# POWER_NODE.net
KiCad netlist of a schematic drawn in Altium Designer
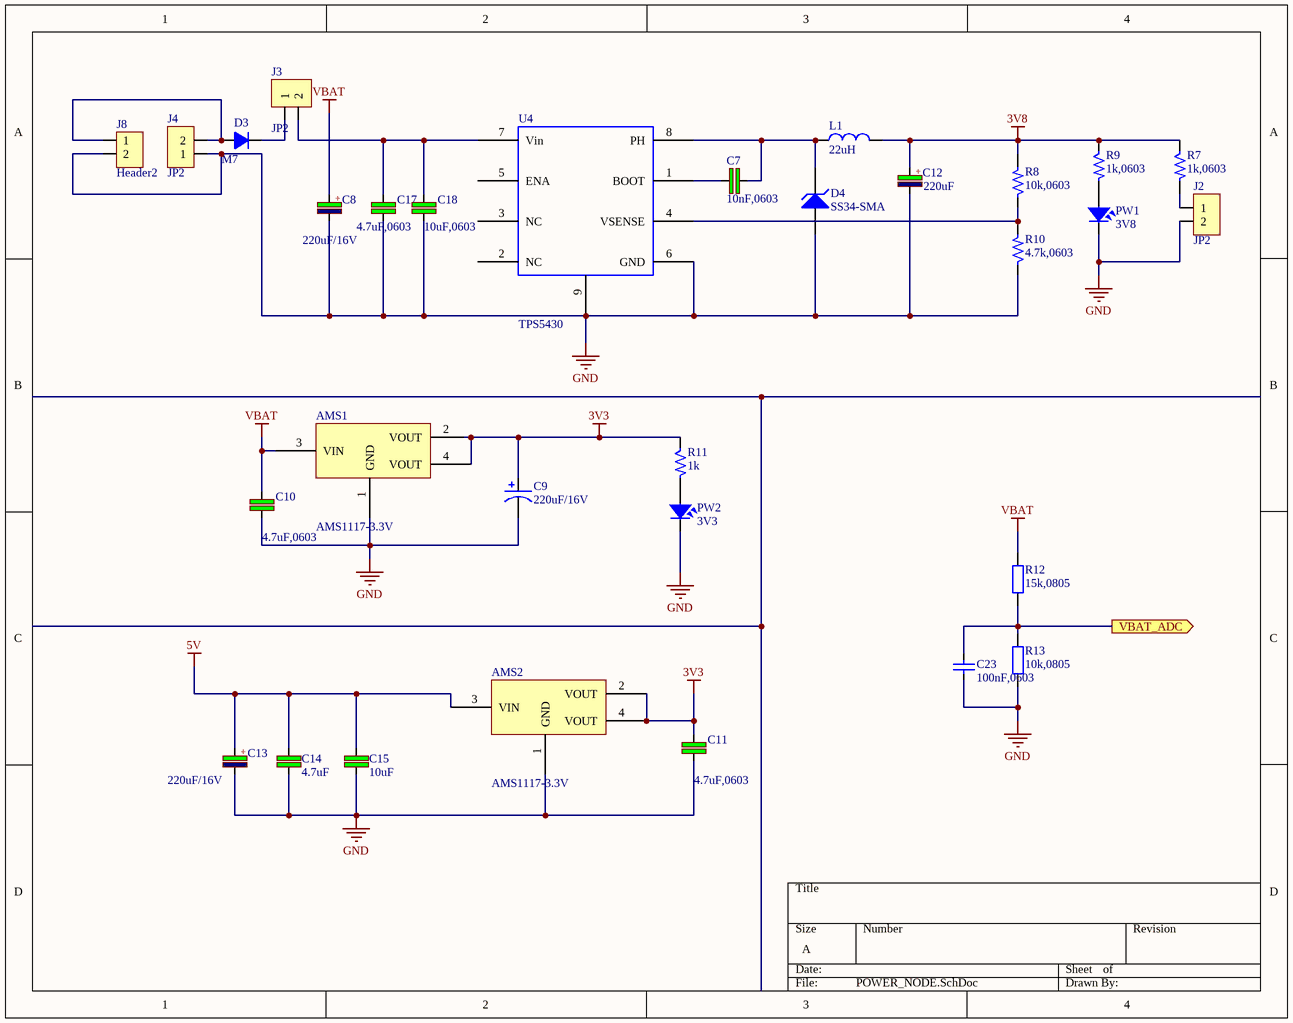
[diagram p0: POWER_NODE.SchDoc]

(export (version "E")
  (design (tool "Eeschema 10.0.6"))
  (components
    (comp (ref "AMS1")
      (value "AMS1117-3.3V")
      (footprint "SOT223")
      (description "Dán")
      (libsource (lib "IC") (part "AMS1117 SMD"))
    )
    (comp (ref "AMS2")
      (value "AMS1117-3.3V")
      (footprint "SOT223")
      (description "Dán")
      (libsource (lib "IC") (part "AMS1117 SMD"))
    )
    (comp (ref "C7")
      (value "10nF,0603")
      (footprint "CAP_0603")
      (description "4.7µF ±10% 35V Ceramic Capacitor X5R 0805 (2012 Metric)")
      (fields
        (field (name "MANUFACTURER") "Samsung Electro-Mechanics")
        (field (name "PART NUMBER") "CL21A475KLCLQNC")
      )
      (libsource (lib "Anh_Trung") (part "C"))
    )
    (comp (ref "C8")
      (value "220uF/16V")
      (footprint "C8mm")
      (description "Cap 470uF/63V")
      (libsource (lib "Main") (part "CP3"))
    )
    (comp (ref "C9")
      (value "220uF/16V")
      (footprint "C5mm")
      (description "Polarized Capacitor (Axial)")
      (fields (field (name "PUBLISHER") "Altium Limited"))
      (libsource (lib "My Library") (part "Cap Pol"))
    )
    (comp (ref "C10")
      (value "4.7uF,0603")
      (footprint "CAP_0603")
      (description "4.7µF ±10% 35V Ceramic Capacitor X5R 0805 (2012 Metric)")
      (fields
        (field (name "MANUFACTURER") "Samsung Electro-Mechanics")
        (field (name "PART NUMBER") "CL21A475KLCLQNC")
      )
      (libsource (lib "") (part "C_1"))
    )
    (comp (ref "C11")
      (value "4.7uF,0603")
      (footprint "CAP_0603")
      (description "4.7µF ±10% 35V Ceramic Capacitor X5R 0805 (2012 Metric)")
      (fields
        (field (name "MANUFACTURER") "Samsung Electro-Mechanics")
        (field (name "PART NUMBER") "CL21A475KLCLQNC")
      )
      (libsource (lib "") (part "C_1"))
    )
    (comp (ref "C12")
      (value "220uF")
      (footprint "C5mm")
      (description "220µF Molded Tantalum Polymer Capacitor 16V 2917 (7343 Metric) 40mOhm @ 100kHz")
      (fields
        (field (name "MANUFACTURER") "AVX Corporation")
        (field (name "PART NUMBER") "TCME227M016R0040E")
      )
      (libsource (lib "Anh_Trung") (part "CP5"))
    )
    (comp (ref "C13")
      (value "220uF/16V")
      (footprint "C8mm")
      (description "Cap 470uF/63V")
      (libsource (lib "Main") (part "CP3"))
    )
    (comp (ref "C14")
      (value "4.7uF")
      (footprint "CAP_0603")
      (description "Cap SMD")
      (fields
        (field (name "MANUFACTURER") "Samsung Electro-Mechanics")
        (field (name "PART NUMBER") "CL21A106KPFNNNG")
      )
      (libsource (lib "Anh_Trung") (part "C"))
    )
    (comp (ref "C15")
      (value "10uF")
      (footprint "CAP_0603")
      (description "Cap SMD")
      (fields
        (field (name "MANUFACTURER") "Samsung Electro-Mechanics")
        (field (name "PART NUMBER") "CL21A106KPFNNNG")
      )
      (libsource (lib "Anh_Trung") (part "C"))
    )
    (comp (ref "C17")
      (value "4.7uF,0603")
      (footprint "CAP_0603")
      (description "4.7µF ±10% 35V Ceramic Capacitor X5R 0805 (2012 Metric)")
      (fields
        (field (name "MANUFACTURER") "Samsung Electro-Mechanics")
        (field (name "PART NUMBER") "CL21A475KLCLQNC")
      )
      (libsource (lib "") (part "C_1"))
    )
    (comp (ref "C18")
      (value "10uF,0603")
      (footprint "CAP_0603")
      (description "4.7µF ±10% 35V Ceramic Capacitor X5R 0805 (2012 Metric)")
      (fields
        (field (name "MANUFACTURER") "Samsung Electro-Mechanics")
        (field (name "PART NUMBER") "CL21A475KLCLQNC")
      )
      (libsource (lib "") (part "C_1"))
    )
    (comp (ref "C23")
      (value "100nF,0603")
      (footprint "CAP_0603")
      (description "Capacitor")
      (fields (field (name "PUBLISHER") "Altium Limited"))
      (libsource (lib "My Library") (part "CapSMD"))
    )
    (comp (ref "D3")
      (value "M7")
      (footprint "SMA")
      (description "Diode 1A")
      (libsource (lib "Main") (part "D1A"))
    )
    (comp (ref "D4")
      (value "SS34-SMA")
      (footprint "SMA")
      (description "Zener Diode")
      (fields (field (name "PUBLISHER") "Altium Limited"))
      (libsource (lib "My Library 2") (part "Diode Zener"))
    )
    (comp (ref "J2")
      (value "JP2")
      (footprint "JP2-D1T")
      (description "WR-PHD 2.54 mm Angled Socket Header")
      (fields
        (field (name "MANUFACTURER") "Würth Elektronik eiSos GmbH")
        (field (name "PARTNO") "613002143121")
        (field (name "CREATED BY") "Karrer Zheng")
      )
      (libsource (lib "") (part "JP2_1"))
    )
    (comp (ref "J3")
      (value "JP2")
      (footprint "KF2-5.08")
      (description "WR-PHD 2.54 mm Angled Socket Header")
      (fields
        (field (name "MANUFACTURER") "Würth Elektronik eiSos GmbH")
        (field (name "PARTNO") "613002143121")
        (field (name "CREATED BY") "Karrer Zheng")
      )
      (libsource (lib "My Library") (part "JP2"))
    )
    (comp (ref "J4")
      (value "JP2")
      (footprint "KF2-5.08")
      (description "WR-PHD 2.54 mm Angled Socket Header")
      (fields
        (field (name "MANUFACTURER") "Würth Elektronik eiSos GmbH")
        (field (name "PARTNO") "613002143121")
        (field (name "CREATED BY") "Karrer Zheng")
      )
      (libsource (lib "") (part "JP2_2"))
    )
    (comp (ref "J8")
      (value "Header2")
      (footprint "KF2-5.08")
      (description "Header IDC, 2 x 1 Pin Vertical 2.54mm Pitch (Non-Boxed, Male)")
      (fields
        (field (name "MANUFACTURER") "Würth Elektronik eiSos GmbH")
        (field (name "PARTNO") "613002143121")
        (field (name "CREATED BY") "Karrer Zheng")
      )
      (libsource (lib "My Library 2") (part "Header2"))
    )
    (comp (ref "L1")
      (value "22uH")
      (footprint "L-SMD-M-7.3x4.5")
      (description "22µH Shielded Inductor 1.65A 96mOhm Max Nonstandard")
      (fields (field (name "MANUFACTURER") "Bourns Inc.") (field (name "PART NUMBER") "SRR0745A-220M"))
      (libsource (lib "Main") (part "L1"))
    )
    (comp (ref "PW1")
      (value "3V8")
      (footprint "LED-0805-Blue")
      (description "LED RED DIFFUSED 0805 SMD")
      (fields
        (field (name "MANUFACTURER") "OSRAM Opto Semiconductors Inc.")
        (field (name "PART NUMBER") "LS R976-NR-1")
      )
      (libsource (lib "Anh_Trung") (part "LED"))
    )
    (comp (ref "PW2")
      (value "3V3")
      (footprint "LED-0805-Blue")
      (description "LED RED DIFFUSED 0805 SMD")
      (fields
        (field (name "MANUFACTURER") "OSRAM Opto Semiconductors Inc.")
        (field (name "PART NUMBER") "LS R976-NR-1")
      )
      (libsource (lib "Anh_Trung") (part "LED"))
    )
    (comp (ref "R7")
      (value "1k,0603")
      (footprint "RES-SMD-0603")
      (description "Resistor 1/4W")
      (fields (field (name "MANUFACTURER") "Yageo") (field (name "PART NUMBER") "RC0805FR-071KL"))
      (libsource (lib "Anh_Trung") (part "R"))
    )
    (comp (ref "R8")
      (value "10k,0603")
      (footprint "RES-SMD-0603")
      (description "RES SMD 10K OHM 1% 1/8W 0805")
      (fields (field (name "MANUFACTURER") "Yageo") (field (name "PART NUMBER") "RC0805FR-0710KL"))
      (libsource (lib "Anh_Trung") (part "R"))
    )
    (comp (ref "R9")
      (value "1k,0603")
      (footprint "RES-SMD-0603")
      (description "Resistor 1/4W")
      (fields (field (name "MANUFACTURER") "Yageo") (field (name "PART NUMBER") "RC0805FR-071KL"))
      (libsource (lib "Anh_Trung") (part "R"))
    )
    (comp (ref "R10")
      (value "4.7k,0603")
      (footprint "RES-SMD-0603")
      (description "RES SMD 3.3K OHM 1% 1/8W 0805")
      (fields (field (name "MANUFACTURER") "Yageo") (field (name "PART NUMBER") "RC0805FR-073K3L"))
      (libsource (lib "Anh_Trung") (part "R"))
    )
    (comp (ref "R11")
      (value "1k")
      (footprint "RES-SMD-0603")
      (description "Resistor 1/4W")
      (fields (field (name "MANUFACTURER") "Yageo") (field (name "PART NUMBER") "RC0805FR-071KL"))
      (libsource (lib "Anh_Trung") (part "R"))
    )
    (comp (ref "R12")
      (value "15k,0805")
      (footprint "RES-SMD-0805")
      (description "Resistor SMD")
      (fields
        (field (name "MANUFACTURER") "Generic Components")
        (field (name "PUBLISHER") "Altium Hobart Technology Centre")
      )
      (libsource (lib "My Library") (part "Resistor - SMD"))
    )
    (comp (ref "R13")
      (value "10k,0805")
      (footprint "RES-SMD-0805")
      (description "Resistor SMD")
      (fields
        (field (name "MANUFACTURER") "Generic Components")
        (field (name "PUBLISHER") "Altium Hobart Technology Centre")
      )
      (libsource (lib "My Library") (part "Resistor - SMD"))
    )
    (comp (ref "U4")
      (value "TPS5430")
      (footprint "TPS5430-2")
      (fields (field (name "NAME") "TPS5430"))
      (libsource (lib "My Library 2") (part "TPS5430"))
    )
  )
  (nets
    (net (code "1") (name "/VBAT_ADC") (class "Default")
      (node (ref "C23") (pin "2") (pinfunction "2_2") (pintype "passive"))
      (node (ref "R12") (pin "1") (pinfunction "1_1") (pintype "passive"))
      (node (ref "R13") (pin "2") (pinfunction "2_2") (pintype "passive"))
    )
    (net (code "2") (name "3V3") (class "Default")
      (node (ref "AMS1") (pin "2") (pinfunction "VOUT_2") (pintype "passive"))
      (node (ref "AMS1") (pin "4") (pinfunction "VOUT_4") (pintype "passive"))
      (node (ref "AMS2") (pin "2") (pinfunction "VOUT_2") (pintype "passive"))
      (node (ref "AMS2") (pin "4") (pinfunction "VOUT_4") (pintype "passive"))
      (node (ref "C11") (pin "2") (pinfunction "2_2") (pintype "passive"))
      (node (ref "C9") (pin "1") (pinfunction "1_1") (pintype "passive"))
      (node (ref "R11") (pin "1") (pinfunction "1_1") (pintype "passive"))
    )
    (net (code "3") (name "3V8") (class "Default")
      (node (ref "C12") (pin "1") (pinfunction "1_1") (pintype "passive"))
      (node (ref "L1") (pin "2") (pinfunction "2_2") (pintype "passive"))
      (node (ref "R7") (pin "1") (pinfunction "1_1") (pintype "passive"))
      (node (ref "R8") (pin "2") (pinfunction "2_2") (pintype "passive"))
      (node (ref "R9") (pin "1") (pinfunction "1_1") (pintype "passive"))
    )
    (net (code "4") (name "5V") (class "Default")
      (node (ref "AMS2") (pin "3") (pinfunction "VIN_3") (pintype "passive"))
      (node (ref "C13") (pin "1") (pinfunction "1_1") (pintype "passive"))
      (node (ref "C14") (pin "1") (pinfunction "1_1") (pintype "passive"))
      (node (ref "C15") (pin "1") (pinfunction "1_1") (pintype "passive"))
    )
    (net (code "5") (name "GND") (class "Default")
      (node (ref "AMS1") (pin "1") (pinfunction "GND_1") (pintype "passive"))
      (node (ref "AMS2") (pin "1") (pinfunction "GND_1") (pintype "passive"))
      (node (ref "C10") (pin "1") (pinfunction "1_1") (pintype "passive"))
      (node (ref "C11") (pin "1") (pinfunction "1_1") (pintype "passive"))
      (node (ref "C12") (pin "2") (pinfunction "2_2") (pintype "passive"))
      (node (ref "C13") (pin "2") (pinfunction "2_2") (pintype "passive"))
      (node (ref "C14") (pin "2") (pinfunction "2_2") (pintype "passive"))
      (node (ref "C15") (pin "2") (pinfunction "2_2") (pintype "passive"))
      (node (ref "C17") (pin "1") (pinfunction "1_1") (pintype "passive"))
      (node (ref "C18") (pin "1") (pinfunction "1_1") (pintype "passive"))
      (node (ref "C23") (pin "1") (pinfunction "1_1") (pintype "passive"))
      (node (ref "C8") (pin "2") (pinfunction "2_2") (pintype "passive"))
      (node (ref "C9") (pin "2") (pinfunction "2_2") (pintype "passive"))
      (node (ref "D4") (pin "1") (pinfunction "A_1") (pintype "passive"))
      (node (ref "J2") (pin "2") (pinfunction "2_2") (pintype "passive"))
      (node (ref "J4") (pin "1") (pinfunction "1_1") (pintype "passive"))
      (node (ref "J8") (pin "2") (pinfunction "2_2") (pintype "passive"))
      (node (ref "PW1") (pin "2") (pinfunction "2_2") (pintype "passive"))
      (node (ref "PW2") (pin "2") (pinfunction "2_2") (pintype "passive"))
      (node (ref "R10") (pin "1") (pinfunction "1_1") (pintype "passive"))
      (node (ref "R13") (pin "1") (pinfunction "1_1") (pintype "passive"))
      (node (ref "U4") (pin "6") (pinfunction "GND_6") (pintype "passive"))
      (node (ref "U4") (pin "9") (pinfunction "PWR_PAD_9") (pintype "passive"))
    )
    (net (code "6") (name "Net-(D3-A)") (class "Default")
      (node (ref "D3") (pin "1") (pinfunction "A_1") (pintype "passive"))
      (node (ref "J4") (pin "2") (pinfunction "2_2") (pintype "passive"))
      (node (ref "J8") (pin "1") (pinfunction "1_1") (pintype "passive"))
    )
    (net (code "7") (name "Net-(D3-K)") (class "Default")
      (node (ref "D3") (pin "2") (pinfunction "K_2") (pintype "passive"))
      (node (ref "J3") (pin "1") (pinfunction "1_1") (pintype "passive"))
    )
    (net (code "8") (name "Net-(D4-K)") (class "Default")
      (node (ref "C7") (pin "1") (pinfunction "1_1") (pintype "passive"))
      (node (ref "D4") (pin "2") (pinfunction "K_2") (pintype "passive"))
      (node (ref "L1") (pin "1") (pinfunction "1_1") (pintype "passive"))
      (node (ref "U4") (pin "8") (pinfunction "PH_8") (pintype "passive"))
    )
    (net (code "9") (name "Net-(J2-Pad1)") (class "Default")
      (node (ref "J2") (pin "1") (pinfunction "1_1") (pintype "passive"))
      (node (ref "R7") (pin "2") (pinfunction "2_2") (pintype "passive"))
    )
    (net (code "10") (name "Net-(PW1-Pad1)") (class "Default")
      (node (ref "PW1") (pin "1") (pinfunction "1_1") (pintype "passive"))
      (node (ref "R9") (pin "2") (pinfunction "2_2") (pintype "passive"))
    )
    (net (code "11") (name "Net-(PW2-Pad1)") (class "Default")
      (node (ref "PW2") (pin "1") (pinfunction "1_1") (pintype "passive"))
      (node (ref "R11") (pin "2") (pinfunction "2_2") (pintype "passive"))
    )
    (net (code "12") (name "Net-(U4-BOOT)") (class "Default")
      (node (ref "C7") (pin "2") (pinfunction "2_2") (pintype "passive"))
      (node (ref "U4") (pin "1") (pinfunction "BOOT_1") (pintype "passive"))
    )
    (net (code "13") (name "Net-(U4-VSENSE)") (class "Default")
      (node (ref "R10") (pin "2") (pinfunction "2_2") (pintype "passive"))
      (node (ref "R8") (pin "1") (pinfunction "1_1") (pintype "passive"))
      (node (ref "U4") (pin "4") (pinfunction "VSENSE_4") (pintype "passive"))
    )
    (net (code "14") (name "Net-(U4-Vin)") (class "Default")
      (node (ref "C17") (pin "2") (pinfunction "2_2") (pintype "passive"))
      (node (ref "C18") (pin "2") (pinfunction "2_2") (pintype "passive"))
      (node (ref "J3") (pin "2") (pinfunction "2_2") (pintype "passive"))
      (node (ref "U4") (pin "7") (pinfunction "Vin_7") (pintype "passive"))
    )
    (net (code "15") (name "VBAT") (class "Default")
      (node (ref "AMS1") (pin "3") (pinfunction "VIN_3") (pintype "passive"))
      (node (ref "C10") (pin "2") (pinfunction "2_2") (pintype "passive"))
      (node (ref "C8") (pin "1") (pinfunction "1_1") (pintype "passive"))
      (node (ref "R12") (pin "2") (pinfunction "2_2") (pintype "passive"))
    )
    (net (code "16") (name "unconnected-(U4-ENA-Pad5)") (class "Default")
      (node (ref "U4") (pin "5") (pinfunction "ENA_5") (pintype "passive"))
    )
    (net (code "17") (name "unconnected-(U4-NC-Pad2)") (class "Default")
      (node (ref "U4") (pin "2") (pinfunction "NC_2") (pintype "passive"))
    )
    (net (code "18") (name "unconnected-(U4-NC-Pad3)") (class "Default")
      (node (ref "U4") (pin "3") (pinfunction "NC_3") (pintype "passive"))
    )
  )
)
